# MISC.net
KiCad netlist of a schematic drawn in Altium Designer
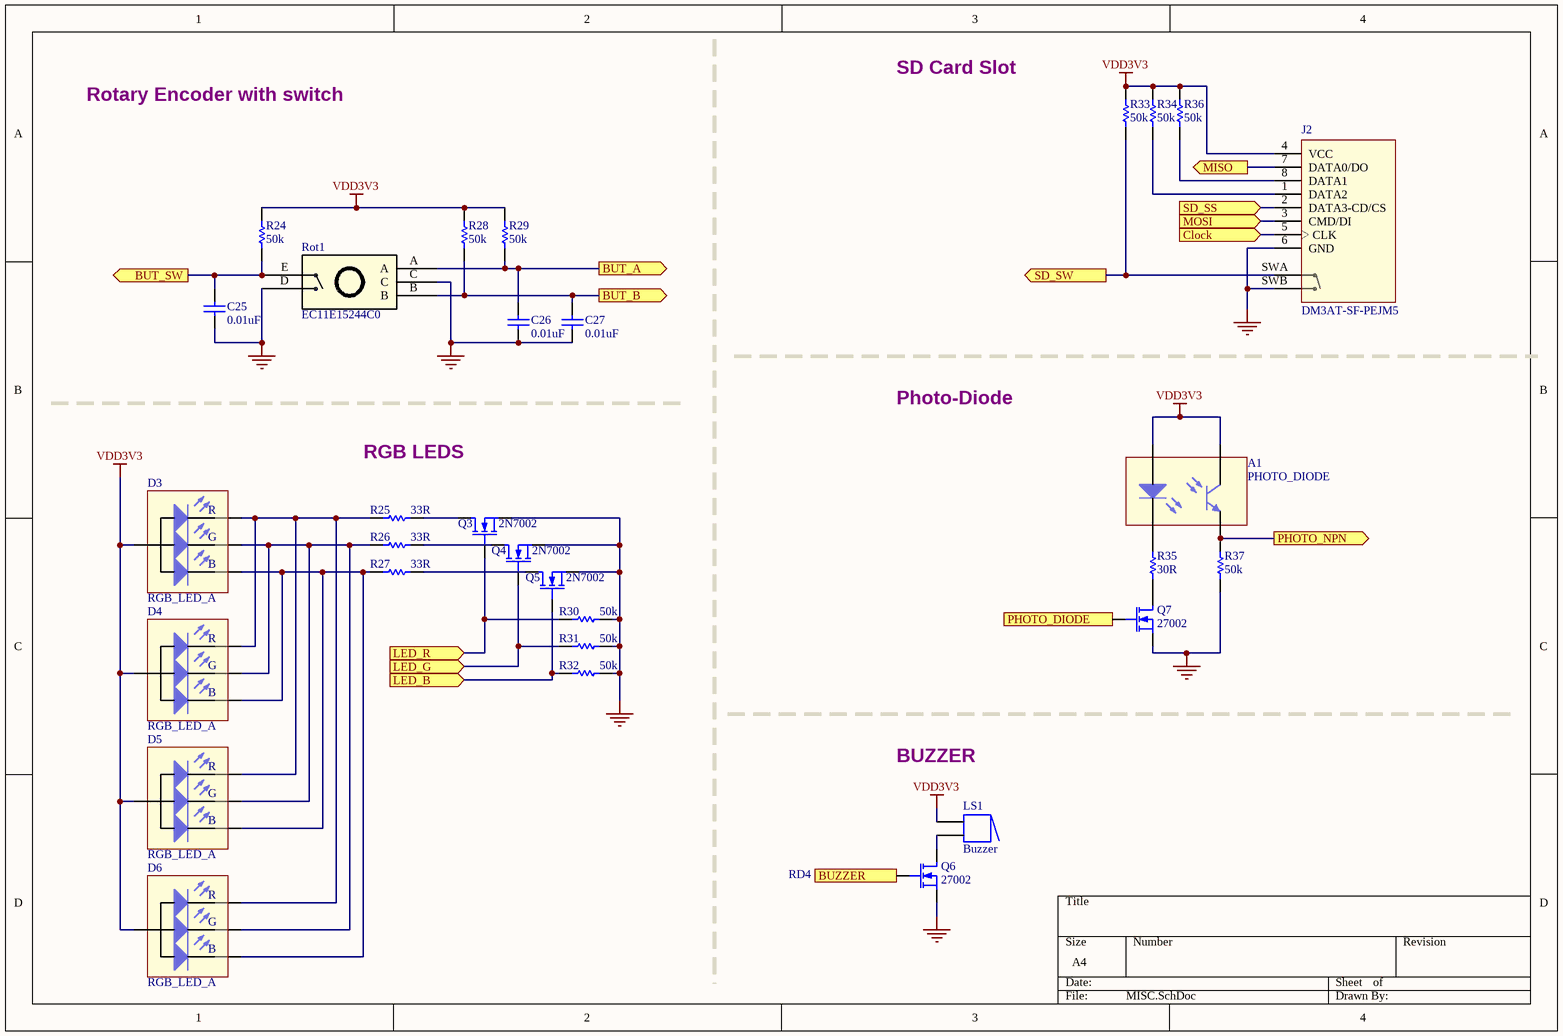
[diagram p0: MISC.SchDoc]

(export (version "E")
  (design (tool "Eeschema 10.0.6"))
  (components
    (comp (ref "A1")
      (value "PHOTO_DIODE")
      (footprint "TCRT5000")
      (description "Photo-diode")
      (libsource (lib "POP_lib") (part "PHOTO_DIODE"))
    )
    (comp (ref "C25")
      (value "0.01uF")
      (footprint "CAPC1608X90N")
      (description "Capacitor")
      (fields (field (name "PUBLISHER") "Altium Limited"))
      (libsource (lib "POP_lib") (part "Capacitor"))
    )
    (comp (ref "C26")
      (value "0.01uF")
      (footprint "CAPC1608X90N")
      (description "Capacitor")
      (fields (field (name "PUBLISHER") "Altium Limited"))
      (libsource (lib "POP_lib") (part "Capacitor"))
    )
    (comp (ref "C27")
      (value "0.01uF")
      (footprint "CAPC1608X90N")
      (description "Capacitor")
      (fields (field (name "PUBLISHER") "Altium Limited"))
      (libsource (lib "POP_lib") (part "Capacitor"))
    )
    (comp (ref "D3")
      (value "RGB_LED_A")
      (footprint "RGB_LED")
      (description "RGB_LED Common Anode")
      (libsource (lib "POP_lib") (part "RGB_LED_A"))
    )
    (comp (ref "D4")
      (value "RGB_LED_A")
      (footprint "RGB_LED")
      (description "RGB_LED Common Anode")
      (libsource (lib "POP_lib") (part "RGB_LED_A"))
    )
    (comp (ref "D5")
      (value "RGB_LED_A")
      (footprint "RGB_LED")
      (description "RGB_LED Common Anode")
      (libsource (lib "POP_lib") (part "RGB_LED_A"))
    )
    (comp (ref "D6")
      (value "RGB_LED_A")
      (footprint "RGB_LED")
      (description "RGB_LED Common Anode")
      (libsource (lib "POP_lib") (part "RGB_LED_A"))
    )
    (comp (ref "J2")
      (value "DM3AT-SF-PEJM5")
      (footprint "HRS_DM3AT-SF-PEJM5_DM3AT-SF-PEJM5(Primary)")
      (description "DM3 RA SMT microSD memory card push/push")
      (libsource (lib "POP_lib") (part "DM3AT-SF-PEJM5"))
    )
    (comp (ref "LS1")
      (value "Buzzer")
      (footprint "ABT-460-RC")
      (description "Magnetic Transducer Buzzer")
      (libsource (lib "POP_lib") (part "Buzzer"))
    )
    (comp (ref "Q3")
      (value "2N7002")
      (footprint "SOT23-3")
      (description "N-Channel MOSFET")
      (libsource (lib "POP_lib") (part "MOSFET-N"))
    )
    (comp (ref "Q4")
      (value "2N7002")
      (footprint "SOT23-3")
      (description "N-Channel MOSFET")
      (libsource (lib "POP_lib") (part "MOSFET-N"))
    )
    (comp (ref "Q5")
      (value "2N7002")
      (footprint "SOT23-3")
      (description "N-Channel MOSFET")
      (libsource (lib "POP_lib") (part "MOSFET-N"))
    )
    (comp (ref "Q6")
      (value "27002")
      (footprint "SOT23-3")
      (description "N-Channel MOSFET")
      (libsource (lib "POP_lib") (part "MOSFET-N"))
    )
    (comp (ref "Q7")
      (value "27002")
      (footprint "SOT23-3")
      (description "N-Channel MOSFET")
      (libsource (lib "POP_lib") (part "MOSFET-N"))
    )
    (comp (ref "R24")
      (value "50k")
      (footprint "RESC1608X55N")
      (description "Resistor")
      (libsource (lib "POP_lib") (part "Resistor"))
    )
    (comp (ref "R25")
      (value "33R")
      (footprint "RESC1608X55N")
      (description "Resistor")
      (libsource (lib "POP_lib") (part "Resistor"))
    )
    (comp (ref "R26")
      (value "33R")
      (footprint "RESC1608X55N")
      (description "Resistor")
      (libsource (lib "POP_lib") (part "Resistor"))
    )
    (comp (ref "R27")
      (value "33R")
      (footprint "RESC1608X55N")
      (description "Resistor")
      (libsource (lib "POP_lib") (part "Resistor"))
    )
    (comp (ref "R28")
      (value "50k")
      (footprint "RESC1608X55N")
      (description "Resistor")
      (libsource (lib "POP_lib") (part "Resistor"))
    )
    (comp (ref "R29")
      (value "50k")
      (footprint "RESC1608X55N")
      (description "Resistor")
      (libsource (lib "POP_lib") (part "Resistor"))
    )
    (comp (ref "R30")
      (value "50k")
      (footprint "RESC1608X55N")
      (description "Resistor")
      (libsource (lib "POP_lib") (part "Resistor"))
    )
    (comp (ref "R31")
      (value "50k")
      (footprint "RESC1608X55N")
      (description "Resistor")
      (libsource (lib "POP_lib") (part "Resistor"))
    )
    (comp (ref "R32")
      (value "50k")
      (footprint "RESC1608X55N")
      (description "Resistor")
      (libsource (lib "POP_lib") (part "Resistor"))
    )
    (comp (ref "R33")
      (value "50k")
      (footprint "RESC1608X55N")
      (description "Resistor")
      (libsource (lib "POP_lib") (part "Resistor"))
    )
    (comp (ref "R34")
      (value "50k")
      (footprint "RESC1608X55N")
      (description "Resistor")
      (libsource (lib "POP_lib") (part "Resistor"))
    )
    (comp (ref "R35")
      (value "30R")
      (footprint "RESC1608X55N")
      (description "Resistor")
      (libsource (lib "POP_lib") (part "Resistor"))
    )
    (comp (ref "R36")
      (value "50k")
      (footprint "RESC1608X55N")
      (description "Resistor")
      (libsource (lib "POP_lib") (part "Resistor"))
    )
    (comp (ref "R37")
      (value "50k")
      (footprint "RESC1608X55N")
      (description "Resistor")
      (libsource (lib "POP_lib") (part "Resistor"))
    )
    (comp (ref "Rot1")
      (value "EC11E15244C0")
      (footprint "EC11E15244C0")
      (description "Rotary Encoder")
      (libsource (lib "POP_lib") (part "EC11E15244C0"))
    )
  )
  (nets
    (net (code "1") (name "/BUT_A") (class "Default")
      (node (ref "C26") (pin "2") (pinfunction "2_2") (pintype "passive"))
      (node (ref "R29") (pin "1") (pinfunction "1_1") (pintype "passive"))
      (node (ref "Rot1") (pin "A") (pinfunction "A_A") (pintype "passive"))
    )
    (net (code "2") (name "/BUT_B") (class "Default")
      (node (ref "C27") (pin "2") (pinfunction "2_2") (pintype "passive"))
      (node (ref "R28") (pin "1") (pinfunction "1_1") (pintype "passive"))
      (node (ref "Rot1") (pin "B") (pinfunction "B_B") (pintype "passive"))
    )
    (net (code "3") (name "/BUT_SW") (class "Default")
      (node (ref "C25") (pin "2") (pinfunction "2_2") (pintype "passive"))
      (node (ref "R24") (pin "1") (pinfunction "1_1") (pintype "passive"))
      (node (ref "Rot1") (pin "E") (pinfunction "Switch_E") (pintype "passive"))
    )
    (net (code "4") (name "/BUZZER") (class "Default")
      (node (ref "Q6") (pin "1") (pinfunction "G_1") (pintype "passive"))
    )
    (net (code "5") (name "/Clock") (class "Default")
      (node (ref "J2") (pin "5") (pinfunction "CLK_5") (pintype "passive"))
    )
    (net (code "6") (name "/LED_B") (class "Default")
      (node (ref "Q5") (pin "1") (pinfunction "G_1") (pintype "passive"))
      (node (ref "R32") (pin "1") (pinfunction "1_1") (pintype "passive"))
    )
    (net (code "7") (name "/LED_G") (class "Default")
      (node (ref "Q4") (pin "1") (pinfunction "G_1") (pintype "passive"))
      (node (ref "R31") (pin "1") (pinfunction "1_1") (pintype "passive"))
    )
    (net (code "8") (name "/LED_R") (class "Default")
      (node (ref "Q3") (pin "1") (pinfunction "G_1") (pintype "passive"))
      (node (ref "R30") (pin "1") (pinfunction "1_1") (pintype "passive"))
    )
    (net (code "9") (name "/MISO") (class "Default")
      (node (ref "J2") (pin "7") (pinfunction "DATA0/DO_7") (pintype "passive"))
    )
    (net (code "10") (name "/MOSI") (class "Default")
      (node (ref "J2") (pin "3") (pinfunction "CMD/DI_3") (pintype "passive"))
    )
    (net (code "11") (name "/PHOTO_DIODE") (class "Default")
      (node (ref "Q7") (pin "1") (pinfunction "G_1") (pintype "passive"))
    )
    (net (code "12") (name "/PHOTO_NPN") (class "Default")
      (node (ref "A1") (pin "1") (pinfunction "1_1") (pintype "passive"))
      (node (ref "R37") (pin "2") (pinfunction "2_2") (pintype "passive"))
    )
    (net (code "13") (name "/SD_SS") (class "Default")
      (node (ref "J2") (pin "2") (pinfunction "DATA3-CD/CS_2") (pintype "passive"))
    )
    (net (code "14") (name "/SD_SW") (class "Default")
      (node (ref "J2") (pin "SWA") (pinfunction "A_SWA") (pintype "passive"))
      (node (ref "R33") (pin "1") (pinfunction "1_1") (pintype "passive"))
    )
    (net (code "15") (name "GND") (class "Default")
      (node (ref "C25") (pin "1") (pinfunction "1_1") (pintype "passive"))
      (node (ref "C26") (pin "1") (pinfunction "1_1") (pintype "passive"))
      (node (ref "C27") (pin "1") (pinfunction "1_1") (pintype "passive"))
      (node (ref "J2") (pin "6") (pinfunction "GND_6") (pintype "passive"))
      (node (ref "J2") (pin "SWB") (pinfunction "B_SWB") (pintype "passive"))
      (node (ref "Q3") (pin "2") (pinfunction "S_2") (pintype "passive"))
      (node (ref "Q4") (pin "2") (pinfunction "S_2") (pintype "passive"))
      (node (ref "Q5") (pin "2") (pinfunction "S_2") (pintype "passive"))
      (node (ref "Q6") (pin "2") (pinfunction "S_2") (pintype "passive"))
      (node (ref "Q7") (pin "2") (pinfunction "S_2") (pintype "passive"))
      (node (ref "R30") (pin "2") (pinfunction "2_2") (pintype "passive"))
      (node (ref "R31") (pin "2") (pinfunction "2_2") (pintype "passive"))
      (node (ref "R32") (pin "2") (pinfunction "2_2") (pintype "passive"))
      (node (ref "R37") (pin "1") (pinfunction "1_1") (pintype "passive"))
      (node (ref "Rot1") (pin "C") (pinfunction "C_C") (pintype "passive"))
      (node (ref "Rot1") (pin "D") (pinfunction "Switch_D") (pintype "passive"))
    )
    (net (code "16") (name "Net-(A1-Pad4)") (class "Default")
      (node (ref "A1") (pin "4") (pinfunction "4_4") (pintype "passive"))
      (node (ref "R35") (pin "2") (pinfunction "2_2") (pintype "passive"))
    )
    (net (code "17") (name "Net-(D3-B)") (class "Default")
      (node (ref "D3") (pin "4") (pinfunction "B_4") (pintype "passive"))
      (node (ref "D4") (pin "4") (pinfunction "B_4") (pintype "passive"))
      (node (ref "D5") (pin "4") (pinfunction "B_4") (pintype "passive"))
      (node (ref "D6") (pin "4") (pinfunction "B_4") (pintype "passive"))
      (node (ref "R27") (pin "1") (pinfunction "1_1") (pintype "passive"))
    )
    (net (code "18") (name "Net-(D3-G)") (class "Default")
      (node (ref "D3") (pin "3") (pinfunction "G_3") (pintype "passive"))
      (node (ref "D4") (pin "3") (pinfunction "G_3") (pintype "passive"))
      (node (ref "D5") (pin "3") (pinfunction "G_3") (pintype "passive"))
      (node (ref "D6") (pin "3") (pinfunction "G_3") (pintype "passive"))
      (node (ref "R26") (pin "1") (pinfunction "1_1") (pintype "passive"))
    )
    (net (code "19") (name "Net-(D3-R)") (class "Default")
      (node (ref "D3") (pin "1") (pinfunction "R_1") (pintype "passive"))
      (node (ref "D4") (pin "1") (pinfunction "R_1") (pintype "passive"))
      (node (ref "D5") (pin "1") (pinfunction "R_1") (pintype "passive"))
      (node (ref "D6") (pin "1") (pinfunction "R_1") (pintype "passive"))
      (node (ref "R25") (pin "1") (pinfunction "1_1") (pintype "passive"))
    )
    (net (code "20") (name "Net-(J2-DATA1)") (class "Default")
      (node (ref "J2") (pin "8") (pinfunction "DATA1_8") (pintype "passive"))
      (node (ref "R36") (pin "1") (pinfunction "1_1") (pintype "passive"))
    )
    (net (code "21") (name "Net-(J2-DATA2)") (class "Default")
      (node (ref "J2") (pin "1") (pinfunction "DATA2_1") (pintype "passive"))
      (node (ref "R34") (pin "1") (pinfunction "1_1") (pintype "passive"))
    )
    (net (code "22") (name "Net-(Q3-D)") (class "Default")
      (node (ref "Q3") (pin "3") (pinfunction "D_3") (pintype "passive"))
      (node (ref "R25") (pin "2") (pinfunction "2_2") (pintype "passive"))
    )
    (net (code "23") (name "Net-(Q4-D)") (class "Default")
      (node (ref "Q4") (pin "3") (pinfunction "D_3") (pintype "passive"))
      (node (ref "R26") (pin "2") (pinfunction "2_2") (pintype "passive"))
    )
    (net (code "24") (name "Net-(Q5-D)") (class "Default")
      (node (ref "Q5") (pin "3") (pinfunction "D_3") (pintype "passive"))
      (node (ref "R27") (pin "2") (pinfunction "2_2") (pintype "passive"))
    )
    (net (code "25") (name "Net-(Q6-D)") (class "Default")
      (node (ref "LS1") (pin "2") (pinfunction "2_2") (pintype "passive"))
      (node (ref "Q6") (pin "3") (pinfunction "D_3") (pintype "passive"))
    )
    (net (code "26") (name "Net-(Q7-D)") (class "Default")
      (node (ref "Q7") (pin "3") (pinfunction "D_3") (pintype "passive"))
      (node (ref "R35") (pin "1") (pinfunction "1_1") (pintype "passive"))
    )
    (net (code "27") (name "VDD3V3") (class "Default")
      (node (ref "A1") (pin "2") (pinfunction "2_2") (pintype "passive"))
      (node (ref "A1") (pin "3") (pinfunction "3_3") (pintype "passive"))
      (node (ref "D3") (pin "2") (pinfunction "Cathode_2") (pintype "passive"))
      (node (ref "D4") (pin "2") (pinfunction "Cathode_2") (pintype "passive"))
      (node (ref "D5") (pin "2") (pinfunction "Cathode_2") (pintype "passive"))
      (node (ref "D6") (pin "2") (pinfunction "Cathode_2") (pintype "passive"))
      (node (ref "J2") (pin "4") (pinfunction "VCC_4") (pintype "passive"))
      (node (ref "LS1") (pin "1") (pinfunction "1_1") (pintype "passive"))
      (node (ref "R24") (pin "2") (pinfunction "2_2") (pintype "passive"))
      (node (ref "R28") (pin "2") (pinfunction "2_2") (pintype "passive"))
      (node (ref "R29") (pin "2") (pinfunction "2_2") (pintype "passive"))
      (node (ref "R33") (pin "2") (pinfunction "2_2") (pintype "passive"))
      (node (ref "R34") (pin "2") (pinfunction "2_2") (pintype "passive"))
      (node (ref "R36") (pin "2") (pinfunction "2_2") (pintype "passive"))
    )
  )
)
